# Sterownik_DC.net
KiCad netlist of a schematic drawn in EAGLE
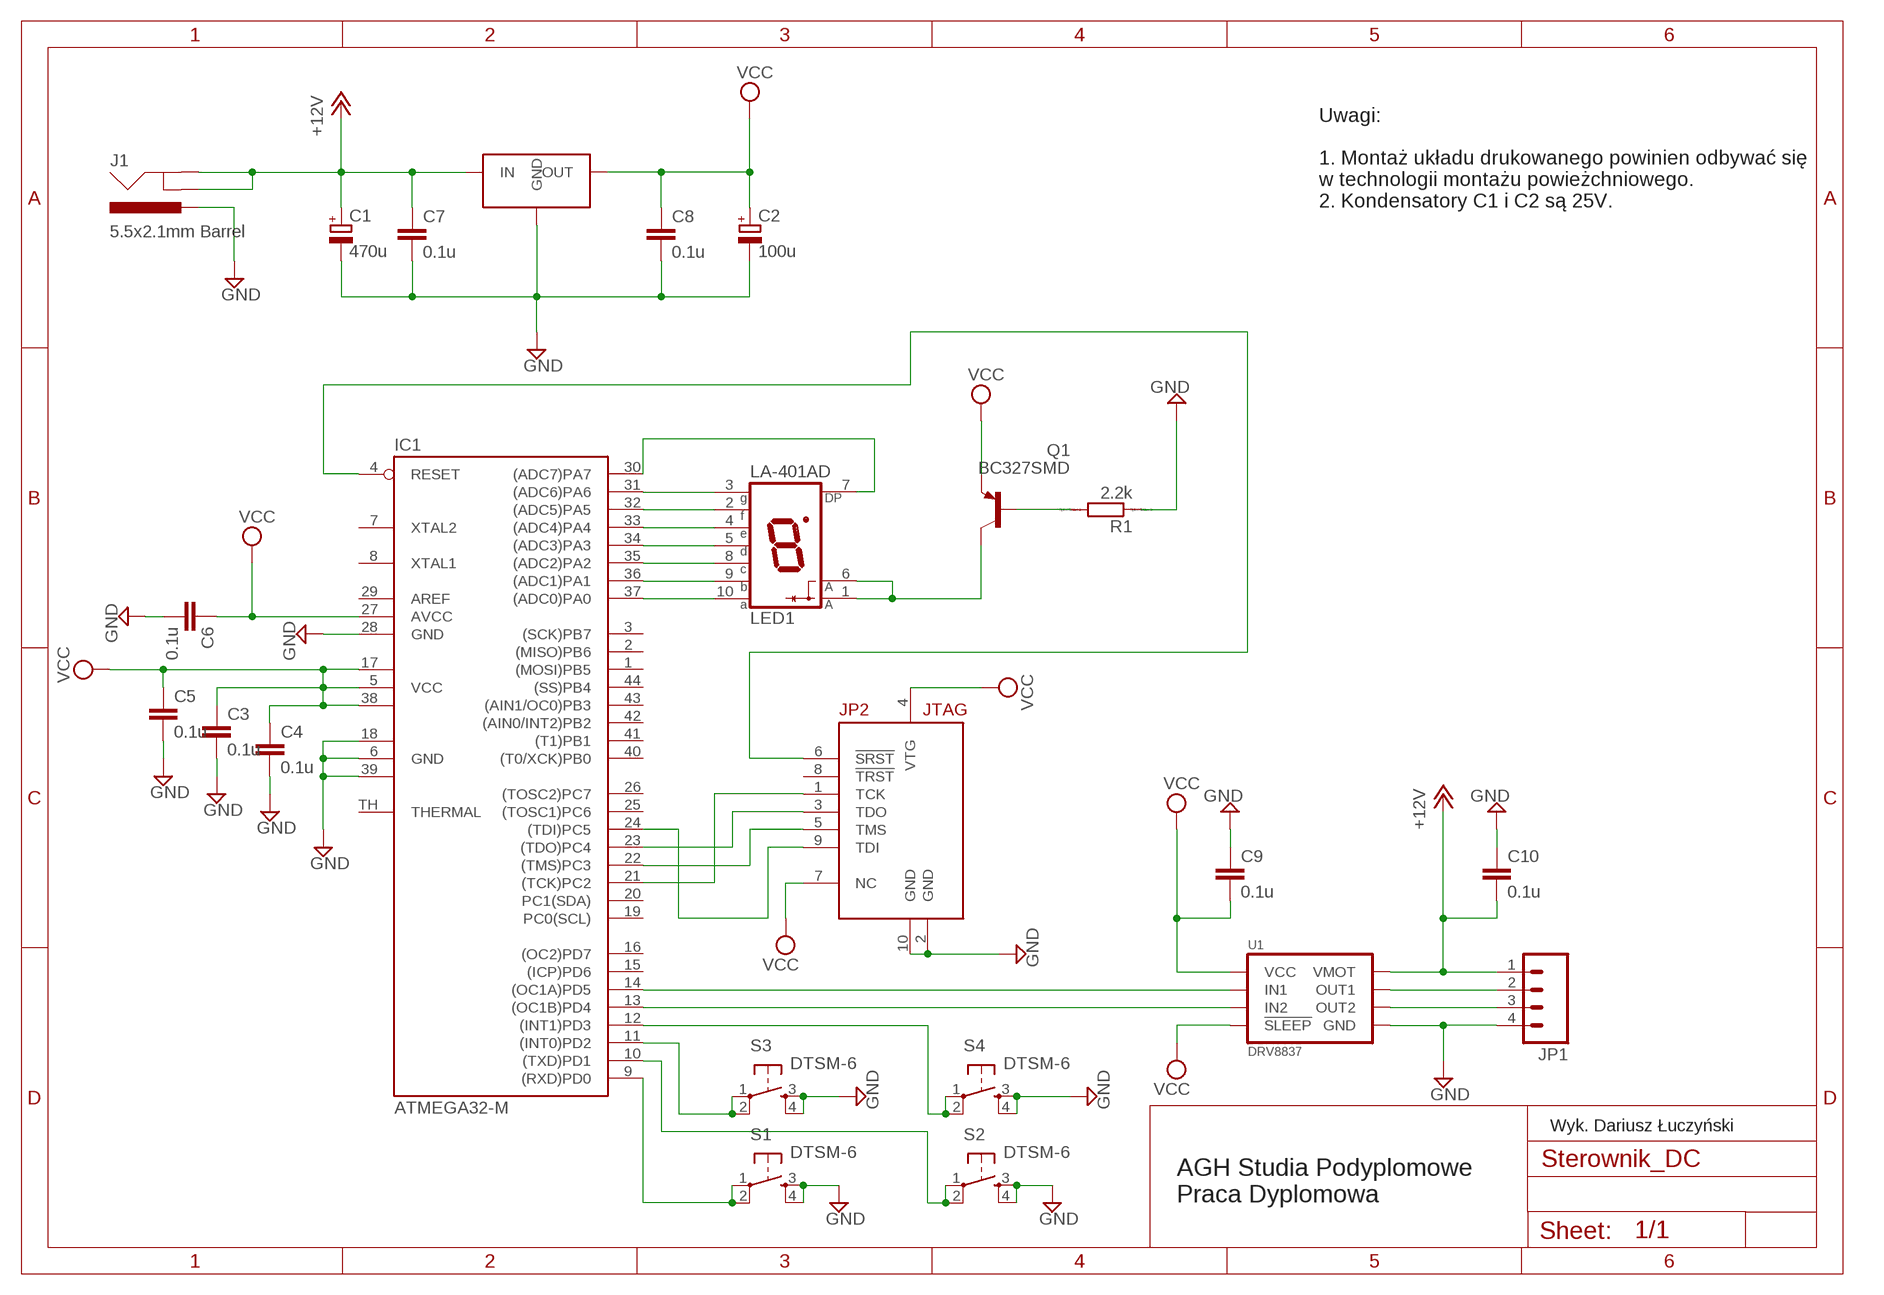
[diagram p0: schematic, sheet 1]

(export (version "E")
  (design (tool "Eeschema 10.0.6"))
  (components
    (comp (ref "C1")
      (value "470u")
      (footprint "eagle-import:175TMP-0810")
      (libsource (lib "eagle-import") (part "CPOL-EU175TMP-0810"))
    )
    (comp (ref "C2")
      (value "100u")
      (footprint "eagle-import:175TMP-0810")
      (libsource (lib "eagle-import") (part "CPOL-EU175TMP-0810"))
    )
    (comp (ref "C3")
      (value "0.1u")
      (footprint "eagle-import:C2012")
      (libsource (lib "eagle-import") (part "C-EUC2012"))
    )
    (comp (ref "C4")
      (value "0.1u")
      (footprint "eagle-import:C2012")
      (libsource (lib "eagle-import") (part "C-EUC2012"))
    )
    (comp (ref "C5")
      (value "0.1u")
      (footprint "eagle-import:C2012")
      (libsource (lib "eagle-import") (part "C-EUC2012"))
    )
    (comp (ref "C6")
      (value "0.1u")
      (footprint "eagle-import:C2012")
      (libsource (lib "eagle-import") (part "C-EUC2012"))
    )
    (comp (ref "C7")
      (value "0.1u")
      (footprint "eagle-import:C2012")
      (libsource (lib "eagle-import") (part "C-EUC2012"))
    )
    (comp (ref "C8")
      (value "0.1u")
      (footprint "eagle-import:C2012")
      (libsource (lib "eagle-import") (part "C-EUC2012"))
    )
    (comp (ref "C9")
      (value "0.1u")
      (footprint "eagle-import:C2012")
      (libsource (lib "eagle-import") (part "C-EUC2012"))
    )
    (comp (ref "C10")
      (value "0.1u")
      (footprint "eagle-import:C2012")
      (libsource (lib "eagle-import") (part "C-EUC2012"))
    )
    (comp (ref "IC1")
      (value "ATMEGA32-M")
      (footprint "eagle-import:MLF44-TH")
      (fields (field (name "MPN") "ATMEGA32-16MU"))
      (libsource (lib "eagle-import") (part "ATMEGA32-M"))
    )
    (comp (ref "J1")
      (value "5.5x2.1mm Barrel")
      (footprint "eagle-import:POWER_JACK_SMD")
      (libsource (lib "eagle-import") (part "POWER_JACKSMD"))
    )
    (comp (ref "JP1")
      (value "M04SMD_STRAIGHT_COMBO")
      (footprint "eagle-import:1X04_SMD_STRAIGHT_COMBO")
      (libsource (lib "eagle-import") (part "M04SMD_STRAIGHT_COMBO"))
    )
    (comp (ref "JP2")
      (value "JTAGICE3-CONNECTOR50MIL-SMD")
      (footprint "eagle-import:JTAGIC3-50MIL-SMD")
      (libsource (lib "eagle-import") (part "JTAGICE3-CONNECTOR50MIL-SMD"))
    )
    (comp (ref "LED1")
      (value "LA-401AD")
      (footprint "eagle-import:LA-401")
      (libsource (lib "eagle-import") (part "LA-401DA"))
    )
    (comp (ref "Q1")
      (value "BC327SMD")
      (footprint "eagle-import:SOT23-BEC")
      (libsource (lib "eagle-import") (part "BC327SMD"))
    )
    (comp (ref "R1")
      (value "2.2k")
      (footprint "eagle-import:R2012")
      (libsource (lib "eagle-import") (part "RR2012"))
    )
    (comp (ref "S1")
      (value "DTSM-6")
      (footprint "eagle-import:DTSM-6")
      (libsource (lib "eagle-import") (part "DTSM-6"))
    )
    (comp (ref "S2")
      (value "DTSM-6")
      (footprint "eagle-import:DTSM-6")
      (libsource (lib "eagle-import") (part "DTSM-6"))
    )
    (comp (ref "S3")
      (value "DTSM-6")
      (footprint "eagle-import:DTSM-6")
      (libsource (lib "eagle-import") (part "DTSM-6"))
    )
    (comp (ref "S4")
      (value "DTSM-6")
      (footprint "eagle-import:DTSM-6")
      (libsource (lib "eagle-import") (part "DTSM-6"))
    )
    (comp (ref "U$1")
      (value "VREG-7805-DPAK2")
      (footprint "eagle-import:VREG-7805-DPAK2")
      (libsource (lib "eagle-import") (part "VREG-7805-DPAK2"))
    )
    (comp (ref "U1")
      (value "DRV8837")
      (footprint "eagle-import:DSG")
      (libsource (lib "eagle-import") (part "DRV8837"))
    )
  )
  (nets
    (net (code "1") (name "+12V") (class "Default")
      (node (ref "C1") (pin "+") (pinfunction "+_+") (pintype "passive"))
      (node (ref "C10") (pin "2") (pinfunction "2_2") (pintype "passive"))
      (node (ref "C7") (pin "1") (pinfunction "1_1") (pintype "passive"))
      (node (ref "J1") (pin "GND") (pinfunction "GNDBREAK_GND") (pintype "bidirectional"))
      (node (ref "J1") (pin "P$4") (pinfunction "GND_P$4") (pintype "bidirectional"))
      (node (ref "JP1") (pin "1") (pinfunction "1_1") (pintype "passive"))
      (node (ref "U$1") (pin "VIN") (pinfunction "IN_VIN") (pintype "bidirectional"))
      (node (ref "U1") (pin "1") (pinfunction "VMOT_1") (pintype "bidirectional"))
    )
    (net (code "2") (name "GND") (class "Default")
      (node (ref "C1") (pin "-") (pinfunction "-_-") (pintype "passive"))
      (node (ref "C10") (pin "1") (pinfunction "1_1") (pintype "passive"))
      (node (ref "C2") (pin "-") (pinfunction "-_-") (pintype "passive"))
      (node (ref "C3") (pin "2") (pinfunction "2_2") (pintype "passive"))
      (node (ref "C4") (pin "2") (pinfunction "2_2") (pintype "passive"))
      (node (ref "C5") (pin "2") (pinfunction "2_2") (pintype "passive"))
      (node (ref "C6") (pin "2") (pinfunction "2_2") (pintype "passive"))
      (node (ref "C7") (pin "2") (pinfunction "2_2") (pintype "passive"))
      (node (ref "C8") (pin "2") (pinfunction "2_2") (pintype "passive"))
      (node (ref "C9") (pin "1") (pinfunction "1_1") (pintype "passive"))
      (node (ref "IC1") (pin "18") (pinfunction "GND1_18") (pintype "power_in"))
      (node (ref "IC1") (pin "28") (pinfunction "GND_28") (pintype "power_in"))
      (node (ref "IC1") (pin "39") (pinfunction "GND2_39") (pintype "power_in"))
      (node (ref "IC1") (pin "6") (pinfunction "GND_6") (pintype "power_in"))
      (node (ref "J1") (pin "VIN0") (pinfunction "PWR_VIN0") (pintype "bidirectional"))
      (node (ref "JP1") (pin "4") (pinfunction "4_4") (pintype "passive"))
      (node (ref "JP2") (pin "10") (pinfunction "GND_10") (pintype "bidirectional"))
      (node (ref "JP2") (pin "2") (pinfunction "GND_2") (pintype "bidirectional"))
      (node (ref "R1") (pin "1") (pinfunction "1_1") (pintype "passive"))
      (node (ref "S1") (pin "3") (pinfunction "3_3") (pintype "passive"))
      (node (ref "S1") (pin "4") (pinfunction "4_4") (pintype "passive"))
      (node (ref "S2") (pin "3") (pinfunction "3_3") (pintype "passive"))
      (node (ref "S2") (pin "4") (pinfunction "4_4") (pintype "passive"))
      (node (ref "S3") (pin "3") (pinfunction "3_3") (pintype "passive"))
      (node (ref "S3") (pin "4") (pinfunction "4_4") (pintype "passive"))
      (node (ref "S4") (pin "3") (pinfunction "3_3") (pintype "passive"))
      (node (ref "S4") (pin "4") (pinfunction "4_4") (pintype "passive"))
      (node (ref "U$1") (pin "GND") (pinfunction "GND_GND") (pintype "bidirectional"))
      (node (ref "U1") (pin "4") (pinfunction "GND_4") (pintype "bidirectional"))
      (node (ref "U1") (pin "PAD") (pinfunction "GND_PAD") (pintype "bidirectional"))
    )
    (net (code "3") (name "Net-(IC1-(ADC0)PA0)") (class "Default")
      (node (ref "IC1") (pin "37") (pinfunction "(ADC0)PA0_37") (pintype "bidirectional"))
      (node (ref "LED1") (pin "10") (pinfunction "A_10") (pintype "passive"))
    )
    (net (code "4") (name "Net-(IC1-(ADC1)PA1)") (class "Default")
      (node (ref "IC1") (pin "36") (pinfunction "(ADC1)PA1_36") (pintype "bidirectional"))
      (node (ref "LED1") (pin "9") (pinfunction "B_9") (pintype "passive"))
    )
    (net (code "5") (name "Net-(IC1-(ADC2)PA2)") (class "Default")
      (node (ref "IC1") (pin "35") (pinfunction "(ADC2)PA2_35") (pintype "bidirectional"))
      (node (ref "LED1") (pin "8") (pinfunction "C_8") (pintype "passive"))
    )
    (net (code "6") (name "Net-(IC1-(ADC3)PA3)") (class "Default")
      (node (ref "IC1") (pin "34") (pinfunction "(ADC3)PA3_34") (pintype "bidirectional"))
      (node (ref "LED1") (pin "5") (pinfunction "D_5") (pintype "passive"))
    )
    (net (code "7") (name "Net-(IC1-(ADC4)PA4)") (class "Default")
      (node (ref "IC1") (pin "33") (pinfunction "(ADC4)PA4_33") (pintype "bidirectional"))
      (node (ref "LED1") (pin "4") (pinfunction "E_4") (pintype "passive"))
    )
    (net (code "8") (name "Net-(IC1-(ADC5)PA5)") (class "Default")
      (node (ref "IC1") (pin "32") (pinfunction "(ADC5)PA5_32") (pintype "bidirectional"))
      (node (ref "LED1") (pin "2") (pinfunction "F_2") (pintype "passive"))
    )
    (net (code "9") (name "Net-(IC1-(ADC6)PA6)") (class "Default")
      (node (ref "IC1") (pin "31") (pinfunction "(ADC6)PA6_31") (pintype "bidirectional"))
      (node (ref "LED1") (pin "3") (pinfunction "G_3") (pintype "passive"))
    )
    (net (code "10") (name "Net-(IC1-(ADC7)PA7)") (class "Default")
      (node (ref "IC1") (pin "30") (pinfunction "(ADC7)PA7_30") (pintype "bidirectional"))
      (node (ref "LED1") (pin "7") (pinfunction "DP_7") (pintype "passive"))
    )
    (net (code "11") (name "Net-(IC1-(INT0)PD2)") (class "Default")
      (node (ref "IC1") (pin "11") (pinfunction "(INT0)PD2_11") (pintype "bidirectional"))
      (node (ref "S3") (pin "1") (pinfunction "1_1") (pintype "passive"))
      (node (ref "S3") (pin "2") (pinfunction "2_2") (pintype "passive"))
    )
    (net (code "12") (name "Net-(IC1-(INT1)PD3)") (class "Default")
      (node (ref "IC1") (pin "12") (pinfunction "(INT1)PD3_12") (pintype "bidirectional"))
      (node (ref "S4") (pin "1") (pinfunction "1_1") (pintype "passive"))
      (node (ref "S4") (pin "2") (pinfunction "2_2") (pintype "passive"))
    )
    (net (code "13") (name "Net-(IC1-(OC1A)PD5)") (class "Default")
      (node (ref "IC1") (pin "14") (pinfunction "(OC1A)PD5_14") (pintype "bidirectional"))
      (node (ref "U1") (pin "6") (pinfunction "IN1_6") (pintype "bidirectional"))
    )
    (net (code "14") (name "Net-(IC1-(OC1B)PD4)") (class "Default")
      (node (ref "IC1") (pin "13") (pinfunction "(OC1B)PD4_13") (pintype "bidirectional"))
      (node (ref "U1") (pin "5") (pinfunction "IN2_5") (pintype "bidirectional"))
    )
    (net (code "15") (name "Net-(IC1-(RXD)PD0)") (class "Default")
      (node (ref "IC1") (pin "9") (pinfunction "(RXD)PD0_9") (pintype "bidirectional"))
      (node (ref "S1") (pin "1") (pinfunction "1_1") (pintype "passive"))
      (node (ref "S1") (pin "2") (pinfunction "2_2") (pintype "passive"))
    )
    (net (code "16") (name "Net-(IC1-(TCK)PC2)") (class "Default")
      (node (ref "IC1") (pin "21") (pinfunction "(TCK)PC2_21") (pintype "bidirectional"))
      (node (ref "JP2") (pin "1") (pinfunction "TCK_1") (pintype "bidirectional"))
    )
    (net (code "17") (name "Net-(IC1-(TDI)PC5)") (class "Default")
      (node (ref "IC1") (pin "24") (pinfunction "(TDI)PC5_24") (pintype "bidirectional"))
      (node (ref "JP2") (pin "9") (pinfunction "TDI_9") (pintype "bidirectional"))
    )
    (net (code "18") (name "Net-(IC1-(TDO)PC4)") (class "Default")
      (node (ref "IC1") (pin "23") (pinfunction "(TDO)PC4_23") (pintype "bidirectional"))
      (node (ref "JP2") (pin "3") (pinfunction "TDO_3") (pintype "bidirectional"))
    )
    (net (code "19") (name "Net-(IC1-(TMS)PC3)") (class "Default")
      (node (ref "IC1") (pin "22") (pinfunction "(TMS)PC3_22") (pintype "bidirectional"))
      (node (ref "JP2") (pin "5") (pinfunction "TMS_5") (pintype "bidirectional"))
    )
    (net (code "20") (name "Net-(IC1-(TXD)PD1)") (class "Default")
      (node (ref "IC1") (pin "10") (pinfunction "(TXD)PD1_10") (pintype "bidirectional"))
      (node (ref "S2") (pin "1") (pinfunction "1_1") (pintype "passive"))
      (node (ref "S2") (pin "2") (pinfunction "2_2") (pintype "passive"))
    )
    (net (code "21") (name "Net-(IC1-RESET)") (class "Default")
      (node (ref "IC1") (pin "4") (pinfunction "RESET_4") (pintype "input"))
      (node (ref "JP2") (pin "6") (pinfunction "~{SRST}_6") (pintype "bidirectional"))
    )
    (net (code "22") (name "Net-(LED1-A-Pad1)") (class "Default")
      (node (ref "LED1") (pin "1") (pinfunction "A_1") (pintype "passive"))
      (node (ref "LED1") (pin "6") (pinfunction "A_6") (pintype "passive"))
      (node (ref "Q1") (pin "C") (pinfunction "C_C") (pintype "passive"))
    )
    (net (code "23") (name "Net-(Q1-PadB)") (class "Default")
      (node (ref "Q1") (pin "B") (pinfunction "B_B") (pintype "passive"))
      (node (ref "R1") (pin "2") (pinfunction "2_2") (pintype "passive"))
    )
    (net (code "24") (name "Net-(U1-OUT1)") (class "Default")
      (node (ref "JP1") (pin "2") (pinfunction "2_2") (pintype "passive"))
      (node (ref "U1") (pin "2") (pinfunction "OUT1_2") (pintype "bidirectional"))
    )
    (net (code "25") (name "Net-(U1-OUT2)") (class "Default")
      (node (ref "JP1") (pin "3") (pinfunction "3_3") (pintype "passive"))
      (node (ref "U1") (pin "3") (pinfunction "OUT2_3") (pintype "bidirectional"))
    )
    (net (code "26") (name "VCC") (class "Default")
      (node (ref "C2") (pin "+") (pinfunction "+_+") (pintype "passive"))
      (node (ref "C3") (pin "1") (pinfunction "1_1") (pintype "passive"))
      (node (ref "C4") (pin "1") (pinfunction "1_1") (pintype "passive"))
      (node (ref "C5") (pin "1") (pinfunction "1_1") (pintype "passive"))
      (node (ref "C6") (pin "1") (pinfunction "1_1") (pintype "passive"))
      (node (ref "C8") (pin "1") (pinfunction "1_1") (pintype "passive"))
      (node (ref "C9") (pin "2") (pinfunction "2_2") (pintype "passive"))
      (node (ref "IC1") (pin "17") (pinfunction "VCC1_17") (pintype "power_in"))
      (node (ref "IC1") (pin "27") (pinfunction "AVCC_27") (pintype "power_in"))
      (node (ref "IC1") (pin "38") (pinfunction "VCC2_38") (pintype "power_in"))
      (node (ref "IC1") (pin "5") (pinfunction "VCC_5") (pintype "power_in"))
      (node (ref "JP2") (pin "4") (pinfunction "VTG_4") (pintype "bidirectional"))
      (node (ref "JP2") (pin "7") (pinfunction "NC_7") (pintype "bidirectional"))
      (node (ref "Q1") (pin "E") (pinfunction "E_E") (pintype "passive"))
      (node (ref "U$1") (pin "VOUT") (pinfunction "OUT_VOUT") (pintype "bidirectional"))
      (node (ref "U1") (pin "7") (pinfunction "~{SLEEP}_7") (pintype "bidirectional"))
      (node (ref "U1") (pin "8") (pinfunction "VCC_8") (pintype "bidirectional"))
    )
    (net (code "27") (name "unconnected-(IC1-(AIN0{slash}INT2)PB2-Pad42)") (class "Default")
      (node (ref "IC1") (pin "42") (pinfunction "(AIN0/INT2)PB2_42") (pintype "bidirectional"))
    )
    (net (code "28") (name "unconnected-(IC1-(AIN1{slash}OC0)PB3-Pad43)") (class "Default")
      (node (ref "IC1") (pin "43") (pinfunction "(AIN1/OC0)PB3_43") (pintype "bidirectional"))
    )
    (net (code "29") (name "unconnected-(IC1-(ICP)PD6-Pad15)") (class "Default")
      (node (ref "IC1") (pin "15") (pinfunction "(ICP)PD6_15") (pintype "bidirectional"))
    )
    (net (code "30") (name "unconnected-(IC1-(MISO)PB6-Pad2)") (class "Default")
      (node (ref "IC1") (pin "2") (pinfunction "(MISO)PB6_2") (pintype "bidirectional"))
    )
    (net (code "31") (name "unconnected-(IC1-(MOSI)PB5-Pad1)") (class "Default")
      (node (ref "IC1") (pin "1") (pinfunction "(MOSI)PB5_1") (pintype "bidirectional"))
    )
    (net (code "32") (name "unconnected-(IC1-(OC2)PD7-Pad16)") (class "Default")
      (node (ref "IC1") (pin "16") (pinfunction "(OC2)PD7_16") (pintype "bidirectional"))
    )
    (net (code "33") (name "unconnected-(IC1-(SCK)PB7-Pad3)") (class "Default")
      (node (ref "IC1") (pin "3") (pinfunction "(SCK)PB7_3") (pintype "bidirectional"))
    )
    (net (code "34") (name "unconnected-(IC1-(SS)PB4-Pad44)") (class "Default")
      (node (ref "IC1") (pin "44") (pinfunction "(SS)PB4_44") (pintype "bidirectional"))
    )
    (net (code "35") (name "unconnected-(IC1-(T0{slash}XCK)PB0-Pad40)") (class "Default")
      (node (ref "IC1") (pin "40") (pinfunction "(T0/XCK)PB0_40") (pintype "bidirectional"))
    )
    (net (code "36") (name "unconnected-(IC1-(T1)PB1-Pad41)") (class "Default")
      (node (ref "IC1") (pin "41") (pinfunction "(T1)PB1_41") (pintype "bidirectional"))
    )
    (net (code "37") (name "unconnected-(IC1-(TOSC1)PC6-Pad25)") (class "Default")
      (node (ref "IC1") (pin "25") (pinfunction "(TOSC1)PC6_25") (pintype "bidirectional"))
    )
    (net (code "38") (name "unconnected-(IC1-(TOSC2)PC7-Pad26)") (class "Default")
      (node (ref "IC1") (pin "26") (pinfunction "(TOSC2)PC7_26") (pintype "bidirectional"))
    )
    (net (code "39") (name "unconnected-(IC1-AREF-Pad29)") (class "Default")
      (node (ref "IC1") (pin "29") (pinfunction "AREF_29") (pintype "passive"))
    )
    (net (code "40") (name "unconnected-(IC1-PC0(SCL)-Pad19)") (class "Default")
      (node (ref "IC1") (pin "19") (pinfunction "PC0(SCL)_19") (pintype "bidirectional"))
    )
    (net (code "41") (name "unconnected-(IC1-PC1(SDA)-Pad20)") (class "Default")
      (node (ref "IC1") (pin "20") (pinfunction "PC1(SDA)_20") (pintype "bidirectional"))
    )
    (net (code "42") (name "unconnected-(IC1-THERMAL-PadTH)") (class "Default")
      (node (ref "IC1") (pin "TH") (pinfunction "THERMAL_TH") (pintype "input"))
    )
    (net (code "43") (name "unconnected-(IC1-XTAL1-Pad8)") (class "Default")
      (node (ref "IC1") (pin "8") (pinfunction "XTAL1_8") (pintype "bidirectional"))
    )
    (net (code "44") (name "unconnected-(IC1-XTAL2-Pad7)") (class "Default")
      (node (ref "IC1") (pin "7") (pinfunction "XTAL2_7") (pintype "bidirectional"))
    )
    (net (code "45") (name "unconnected-(JP2-~{TRST}-Pad8)") (class "Default")
      (node (ref "JP2") (pin "8") (pinfunction "~{TRST}_8") (pintype "bidirectional"))
    )
  )
)
